# Nano.net
KiCad netlist of a schematic drawn in EAGLE
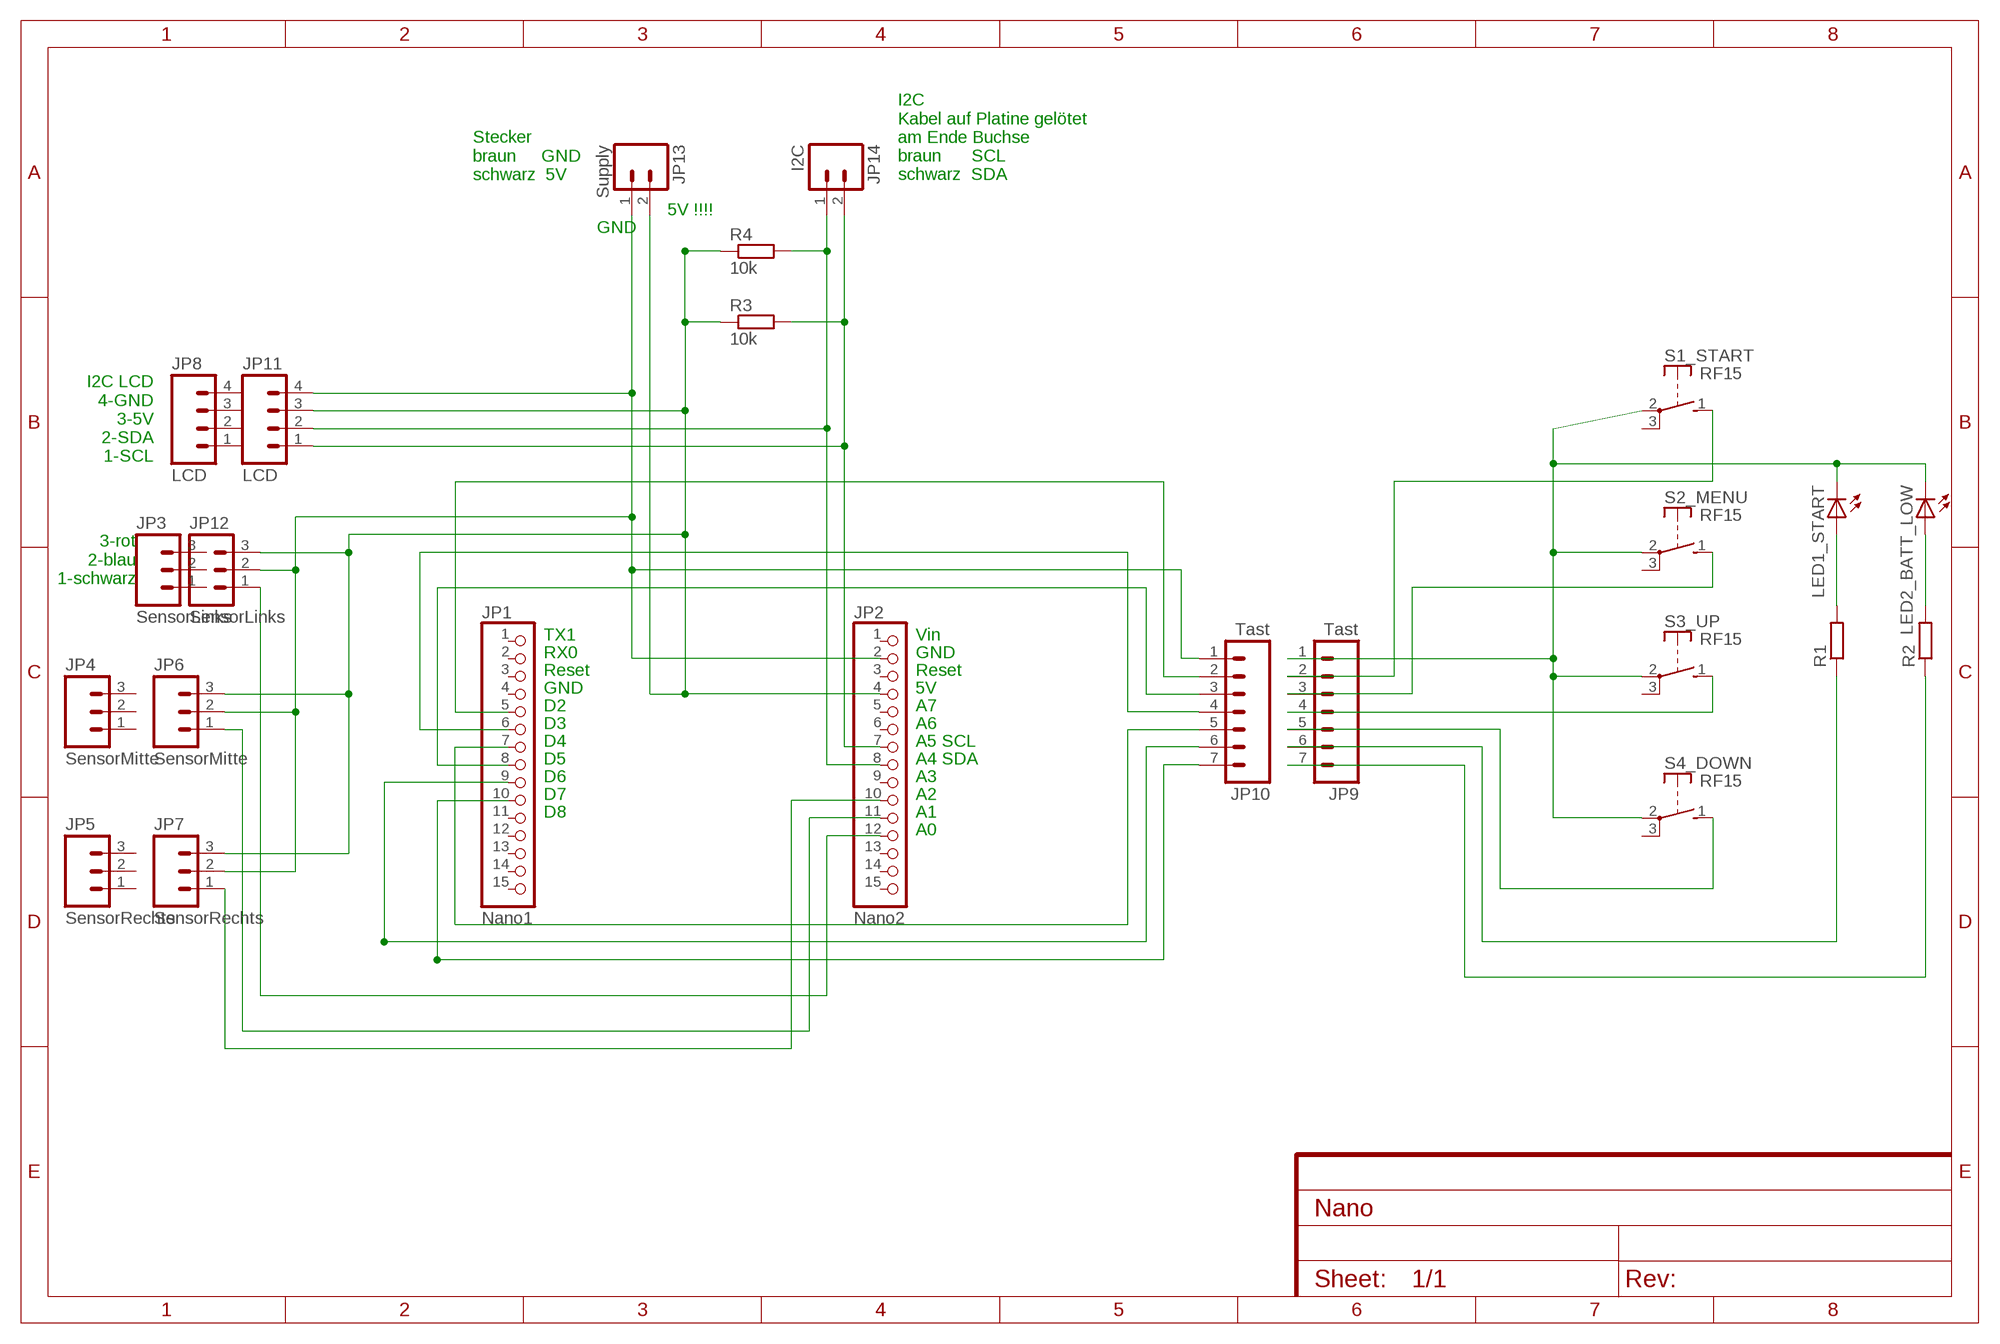
[diagram p0: schematic, sheet 1]

(export (version "E")
  (design (tool "Eeschema 10.0.6"))
  (components
    (comp (ref "JP1")
      (value "Nano1")
      (footprint "eagle-import:1X15")
      (libsource (lib "eagle-import") (part "PINHD-1X15"))
    )
    (comp (ref "JP2")
      (value "Nano2")
      (footprint "eagle-import:1X15")
      (libsource (lib "eagle-import") (part "PINHD-1X15"))
    )
    (comp (ref "JP3")
      (value "SensorLinks")
      (footprint "eagle-import:1X03_LOCK")
      (libsource (lib "eagle-import") (part "M03LOCK"))
    )
    (comp (ref "JP4")
      (value "SensorMitte")
      (footprint "eagle-import:1X03_LOCK")
      (libsource (lib "eagle-import") (part "M03LOCK"))
    )
    (comp (ref "JP5")
      (value "SensorRechts")
      (footprint "eagle-import:1X03_LOCK")
      (libsource (lib "eagle-import") (part "M03LOCK"))
    )
    (comp (ref "JP6")
      (value "SensorMitte")
      (footprint "eagle-import:1X03_LOCK")
      (libsource (lib "eagle-import") (part "M03LOCK"))
    )
    (comp (ref "JP7")
      (value "SensorRechts")
      (footprint "eagle-import:1X03_LOCK")
      (libsource (lib "eagle-import") (part "M03LOCK"))
    )
    (comp (ref "JP8")
      (value "LCD")
      (footprint "eagle-import:1X04_LOCK")
      (libsource (lib "eagle-import") (part "M04LOCK"))
    )
    (comp (ref "JP9")
      (value "Tast")
      (footprint "eagle-import:1X07")
      (libsource (lib "eagle-import") (part "M07"))
    )
    (comp (ref "JP10")
      (value "Tast")
      (footprint "eagle-import:1X07")
      (libsource (lib "eagle-import") (part "M07"))
    )
    (comp (ref "JP11")
      (value "LCD")
      (footprint "eagle-import:1X04_LOCK")
      (libsource (lib "eagle-import") (part "M04LOCK"))
    )
    (comp (ref "JP12")
      (value "SensorLinks")
      (footprint "eagle-import:1X03_LOCK")
      (libsource (lib "eagle-import") (part "M03LOCK"))
    )
    (comp (ref "JP13")
      (value "Supply")
      (footprint "eagle-import:1X02_LOCK")
      (libsource (lib "eagle-import") (part "M02LOCK"))
    )
    (comp (ref "JP14")
      (value "I2C")
      (footprint "eagle-import:1X02_LOCK")
      (libsource (lib "eagle-import") (part "M02LOCK"))
    )
    (comp (ref "LED1_START")
      (value "LED_ELD260")
      (footprint "eagle-import:LED_LD260")
      (libsource (lib "eagle-import") (part "LED_ELD260"))
    )
    (comp (ref "LED2_BATT_LOW")
      (value "LED_ELD260")
      (footprint "eagle-import:LED_LD260")
      (libsource (lib "eagle-import") (part "LED_ELD260"))
    )
    (comp (ref "R1")
      (value "R-EU_0204/5")
      (footprint "eagle-import:0204_5")
      (libsource (lib "eagle-import") (part "R-EU_0204/5"))
    )
    (comp (ref "R2")
      (value "R-EU_0204/5")
      (footprint "eagle-import:0204_5")
      (libsource (lib "eagle-import") (part "R-EU_0204/5"))
    )
    (comp (ref "R3")
      (value "10k")
      (footprint "eagle-import:0204_5")
      (libsource (lib "eagle-import") (part "R-EU_0204/5"))
    )
    (comp (ref "R4")
      (value "10k")
      (footprint "eagle-import:0204_5")
      (libsource (lib "eagle-import") (part "R-EU_0204/5"))
    )
    (comp (ref "S1_START")
      (value "RF15")
      (footprint "eagle-import:RF15")
      (libsource (lib "eagle-import") (part "RF15"))
    )
    (comp (ref "S2_MENU")
      (value "RF15")
      (footprint "eagle-import:RF15")
      (libsource (lib "eagle-import") (part "RF15"))
    )
    (comp (ref "S3_UP")
      (value "RF15")
      (footprint "eagle-import:RF15")
      (libsource (lib "eagle-import") (part "RF15"))
    )
    (comp (ref "S4_DOWN")
      (value "RF15")
      (footprint "eagle-import:RF15")
      (libsource (lib "eagle-import") (part "RF15"))
    )
  )
  (nets
    (net (code "1") (name "Net-(JP1-Pad5)") (class "Default")
      (node (ref "JP1") (pin "5") (pinfunction "5_5") (pintype "passive"))
      (node (ref "JP10") (pin "2") (pinfunction "2_2") (pintype "passive"))
    )
    (net (code "2") (name "Net-(JP1-Pad6)") (class "Default")
      (node (ref "JP1") (pin "6") (pinfunction "6_6") (pintype "passive"))
      (node (ref "JP10") (pin "4") (pinfunction "4_4") (pintype "passive"))
    )
    (net (code "3") (name "Net-(JP1-Pad7)") (class "Default")
      (node (ref "JP1") (pin "7") (pinfunction "7_7") (pintype "passive"))
      (node (ref "JP10") (pin "5") (pinfunction "5_5") (pintype "passive"))
    )
    (net (code "4") (name "Net-(JP1-Pad8)") (class "Default")
      (node (ref "JP1") (pin "8") (pinfunction "8_8") (pintype "passive"))
      (node (ref "JP10") (pin "3") (pinfunction "3_3") (pintype "passive"))
    )
    (net (code "5") (name "Net-(JP1-Pad9)") (class "Default")
      (node (ref "JP1") (pin "9") (pinfunction "9_9") (pintype "passive"))
      (node (ref "JP10") (pin "6") (pinfunction "6_6") (pintype "passive"))
    )
    (net (code "6") (name "Net-(JP1-Pad10)") (class "Default")
      (node (ref "JP1") (pin "10") (pinfunction "10_10") (pintype "passive"))
      (node (ref "JP10") (pin "7") (pinfunction "7_7") (pintype "passive"))
    )
    (net (code "7") (name "Net-(JP2-Pad10)") (class "Default")
      (node (ref "JP2") (pin "10") (pinfunction "10_10") (pintype "passive"))
      (node (ref "JP7") (pin "1") (pinfunction "1_1") (pintype "passive"))
    )
    (net (code "8") (name "Net-(JP2-Pad11)") (class "Default")
      (node (ref "JP2") (pin "11") (pinfunction "11_11") (pintype "passive"))
      (node (ref "JP6") (pin "1") (pinfunction "1_1") (pintype "passive"))
    )
    (net (code "9") (name "Net-(JP9-Pad6)") (class "Default")
      (node (ref "JP9") (pin "6") (pinfunction "6_6") (pintype "passive"))
      (node (ref "R1") (pin "1") (pinfunction "1_1") (pintype "passive"))
    )
    (net (code "10") (name "Net-(JP9-Pad7)") (class "Default")
      (node (ref "JP9") (pin "7") (pinfunction "7_7") (pintype "passive"))
      (node (ref "R2") (pin "1") (pinfunction "1_1") (pintype "passive"))
    )
    (net (code "11") (name "Net-(JP10-Pad1)") (class "Default")
      (node (ref "JP10") (pin "1") (pinfunction "1_1") (pintype "passive"))
      (node (ref "JP11") (pin "4") (pinfunction "4_4") (pintype "passive"))
      (node (ref "JP12") (pin "2") (pinfunction "2_2") (pintype "passive"))
      (node (ref "JP13") (pin "1") (pinfunction "1_1") (pintype "passive"))
      (node (ref "JP2") (pin "2") (pinfunction "2_2") (pintype "passive"))
      (node (ref "JP6") (pin "2") (pinfunction "2_2") (pintype "passive"))
      (node (ref "JP7") (pin "2") (pinfunction "2_2") (pintype "passive"))
    )
    (net (code "12") (name "Net-(JP11-Pad1)") (class "Default")
      (node (ref "JP11") (pin "1") (pinfunction "1_1") (pintype "passive"))
      (node (ref "JP14") (pin "2") (pinfunction "2_2") (pintype "passive"))
      (node (ref "JP2") (pin "7") (pinfunction "7_7") (pintype "passive"))
      (node (ref "R3") (pin "2") (pinfunction "2_2") (pintype "passive"))
    )
    (net (code "13") (name "Net-(JP11-Pad2)") (class "Default")
      (node (ref "JP11") (pin "2") (pinfunction "2_2") (pintype "passive"))
      (node (ref "JP14") (pin "1") (pinfunction "1_1") (pintype "passive"))
      (node (ref "JP2") (pin "8") (pinfunction "8_8") (pintype "passive"))
      (node (ref "R4") (pin "2") (pinfunction "2_2") (pintype "passive"))
    )
    (net (code "14") (name "Net-(JP11-Pad3)") (class "Default")
      (node (ref "JP11") (pin "3") (pinfunction "3_3") (pintype "passive"))
      (node (ref "JP12") (pin "3") (pinfunction "3_3") (pintype "passive"))
      (node (ref "JP13") (pin "2") (pinfunction "2_2") (pintype "passive"))
      (node (ref "JP2") (pin "4") (pinfunction "4_4") (pintype "passive"))
      (node (ref "JP6") (pin "3") (pinfunction "3_3") (pintype "passive"))
      (node (ref "JP7") (pin "3") (pinfunction "3_3") (pintype "passive"))
      (node (ref "R3") (pin "1") (pinfunction "1_1") (pintype "passive"))
      (node (ref "R4") (pin "1") (pinfunction "1_1") (pintype "passive"))
    )
    (net (code "15") (name "Net-(JP12-Pad1)") (class "Default")
      (node (ref "JP12") (pin "1") (pinfunction "1_1") (pintype "passive"))
      (node (ref "JP2") (pin "12") (pinfunction "12_12") (pintype "passive"))
    )
    (net (code "16") (name "Net-(LED1_START-C)") (class "Default")
      (node (ref "JP9") (pin "1") (pinfunction "1_1") (pintype "passive"))
      (node (ref "LED1_START") (pin "K") (pinfunction "C_K") (pintype "passive"))
      (node (ref "LED2_BATT_LOW") (pin "K") (pinfunction "C_K") (pintype "passive"))
      (node (ref "S1_START") (pin "2") (pinfunction "P_2") (pintype "passive"))
      (node (ref "S2_MENU") (pin "2") (pinfunction "P_2") (pintype "passive"))
      (node (ref "S3_UP") (pin "2") (pinfunction "P_2") (pintype "passive"))
      (node (ref "S4_DOWN") (pin "2") (pinfunction "P_2") (pintype "passive"))
    )
    (net (code "17") (name "Net-(LED1_START-PadA)") (class "Default")
      (node (ref "LED1_START") (pin "A") (pinfunction "A_A") (pintype "passive"))
      (node (ref "R1") (pin "2") (pinfunction "2_2") (pintype "passive"))
    )
    (net (code "18") (name "Net-(LED2_BATT_LOW-PadA)") (class "Default")
      (node (ref "LED2_BATT_LOW") (pin "A") (pinfunction "A_A") (pintype "passive"))
      (node (ref "R2") (pin "2") (pinfunction "2_2") (pintype "passive"))
    )
    (net (code "19") (name "Net-(S1_START-S)") (class "Default")
      (node (ref "JP9") (pin "2") (pinfunction "2_2") (pintype "passive"))
      (node (ref "S1_START") (pin "1") (pinfunction "S_1") (pintype "passive"))
    )
    (net (code "20") (name "Net-(S2_MENU-S)") (class "Default")
      (node (ref "JP9") (pin "3") (pinfunction "3_3") (pintype "passive"))
      (node (ref "S2_MENU") (pin "1") (pinfunction "S_1") (pintype "passive"))
    )
    (net (code "21") (name "Net-(S3_UP-S)") (class "Default")
      (node (ref "JP9") (pin "4") (pinfunction "4_4") (pintype "passive"))
      (node (ref "S3_UP") (pin "1") (pinfunction "S_1") (pintype "passive"))
    )
    (net (code "22") (name "Net-(S4_DOWN-S)") (class "Default")
      (node (ref "JP9") (pin "5") (pinfunction "5_5") (pintype "passive"))
      (node (ref "S4_DOWN") (pin "1") (pinfunction "S_1") (pintype "passive"))
    )
    (net (code "23") (name "unconnected-(JP1-Pad1)") (class "Default")
      (node (ref "JP1") (pin "1") (pinfunction "1_1") (pintype "passive"))
    )
    (net (code "24") (name "unconnected-(JP1-Pad2)") (class "Default")
      (node (ref "JP1") (pin "2") (pinfunction "2_2") (pintype "passive"))
    )
    (net (code "25") (name "unconnected-(JP1-Pad3)") (class "Default")
      (node (ref "JP1") (pin "3") (pinfunction "3_3") (pintype "passive"))
    )
    (net (code "26") (name "unconnected-(JP1-Pad4)") (class "Default")
      (node (ref "JP1") (pin "4") (pinfunction "4_4") (pintype "passive"))
    )
    (net (code "27") (name "unconnected-(JP1-Pad11)") (class "Default")
      (node (ref "JP1") (pin "11") (pinfunction "11_11") (pintype "passive"))
    )
    (net (code "28") (name "unconnected-(JP1-Pad12)") (class "Default")
      (node (ref "JP1") (pin "12") (pinfunction "12_12") (pintype "passive"))
    )
    (net (code "29") (name "unconnected-(JP1-Pad13)") (class "Default")
      (node (ref "JP1") (pin "13") (pinfunction "13_13") (pintype "passive"))
    )
    (net (code "30") (name "unconnected-(JP1-Pad14)") (class "Default")
      (node (ref "JP1") (pin "14") (pinfunction "14_14") (pintype "passive"))
    )
    (net (code "31") (name "unconnected-(JP1-Pad15)") (class "Default")
      (node (ref "JP1") (pin "15") (pinfunction "15_15") (pintype "passive"))
    )
    (net (code "32") (name "unconnected-(JP2-Pad1)") (class "Default")
      (node (ref "JP2") (pin "1") (pinfunction "1_1") (pintype "passive"))
    )
    (net (code "33") (name "unconnected-(JP2-Pad3)") (class "Default")
      (node (ref "JP2") (pin "3") (pinfunction "3_3") (pintype "passive"))
    )
    (net (code "34") (name "unconnected-(JP2-Pad5)") (class "Default")
      (node (ref "JP2") (pin "5") (pinfunction "5_5") (pintype "passive"))
    )
    (net (code "35") (name "unconnected-(JP2-Pad6)") (class "Default")
      (node (ref "JP2") (pin "6") (pinfunction "6_6") (pintype "passive"))
    )
    (net (code "36") (name "unconnected-(JP2-Pad9)") (class "Default")
      (node (ref "JP2") (pin "9") (pinfunction "9_9") (pintype "passive"))
    )
    (net (code "37") (name "unconnected-(JP2-Pad13)") (class "Default")
      (node (ref "JP2") (pin "13") (pinfunction "13_13") (pintype "passive"))
    )
    (net (code "38") (name "unconnected-(JP2-Pad14)") (class "Default")
      (node (ref "JP2") (pin "14") (pinfunction "14_14") (pintype "passive"))
    )
    (net (code "39") (name "unconnected-(JP2-Pad15)") (class "Default")
      (node (ref "JP2") (pin "15") (pinfunction "15_15") (pintype "passive"))
    )
    (net (code "40") (name "unconnected-(JP3-Pad1)") (class "Default")
      (node (ref "JP3") (pin "1") (pinfunction "1_1") (pintype "passive"))
    )
    (net (code "41") (name "unconnected-(JP3-Pad2)") (class "Default")
      (node (ref "JP3") (pin "2") (pinfunction "2_2") (pintype "passive"))
    )
    (net (code "42") (name "unconnected-(JP3-Pad3)") (class "Default")
      (node (ref "JP3") (pin "3") (pinfunction "3_3") (pintype "passive"))
    )
    (net (code "43") (name "unconnected-(JP4-Pad1)") (class "Default")
      (node (ref "JP4") (pin "1") (pinfunction "1_1") (pintype "passive"))
    )
    (net (code "44") (name "unconnected-(JP4-Pad2)") (class "Default")
      (node (ref "JP4") (pin "2") (pinfunction "2_2") (pintype "passive"))
    )
    (net (code "45") (name "unconnected-(JP4-Pad3)") (class "Default")
      (node (ref "JP4") (pin "3") (pinfunction "3_3") (pintype "passive"))
    )
    (net (code "46") (name "unconnected-(JP5-Pad1)") (class "Default")
      (node (ref "JP5") (pin "1") (pinfunction "1_1") (pintype "passive"))
    )
    (net (code "47") (name "unconnected-(JP5-Pad2)") (class "Default")
      (node (ref "JP5") (pin "2") (pinfunction "2_2") (pintype "passive"))
    )
    (net (code "48") (name "unconnected-(JP5-Pad3)") (class "Default")
      (node (ref "JP5") (pin "3") (pinfunction "3_3") (pintype "passive"))
    )
    (net (code "49") (name "unconnected-(JP8-Pad1)") (class "Default")
      (node (ref "JP8") (pin "1") (pinfunction "1_1") (pintype "passive"))
    )
    (net (code "50") (name "unconnected-(JP8-Pad2)") (class "Default")
      (node (ref "JP8") (pin "2") (pinfunction "2_2") (pintype "passive"))
    )
    (net (code "51") (name "unconnected-(JP8-Pad3)") (class "Default")
      (node (ref "JP8") (pin "3") (pinfunction "3_3") (pintype "passive"))
    )
    (net (code "52") (name "unconnected-(JP8-Pad4)") (class "Default")
      (node (ref "JP8") (pin "4") (pinfunction "4_4") (pintype "passive"))
    )
    (net (code "53") (name "unconnected-(S1_START-P-Pad3)") (class "Default")
      (node (ref "S1_START") (pin "3") (pinfunction "P_3") (pintype "passive"))
    )
    (net (code "54") (name "unconnected-(S2_MENU-P-Pad3)") (class "Default")
      (node (ref "S2_MENU") (pin "3") (pinfunction "P_3") (pintype "passive"))
    )
    (net (code "55") (name "unconnected-(S3_UP-P-Pad3)") (class "Default")
      (node (ref "S3_UP") (pin "3") (pinfunction "P_3") (pintype "passive"))
    )
    (net (code "56") (name "unconnected-(S4_DOWN-P-Pad3)") (class "Default")
      (node (ref "S4_DOWN") (pin "3") (pinfunction "P_3") (pintype "passive"))
    )
  )
)
